# relay_interface_v4.net
KiCad netlist of a schematic drawn in EAGLE
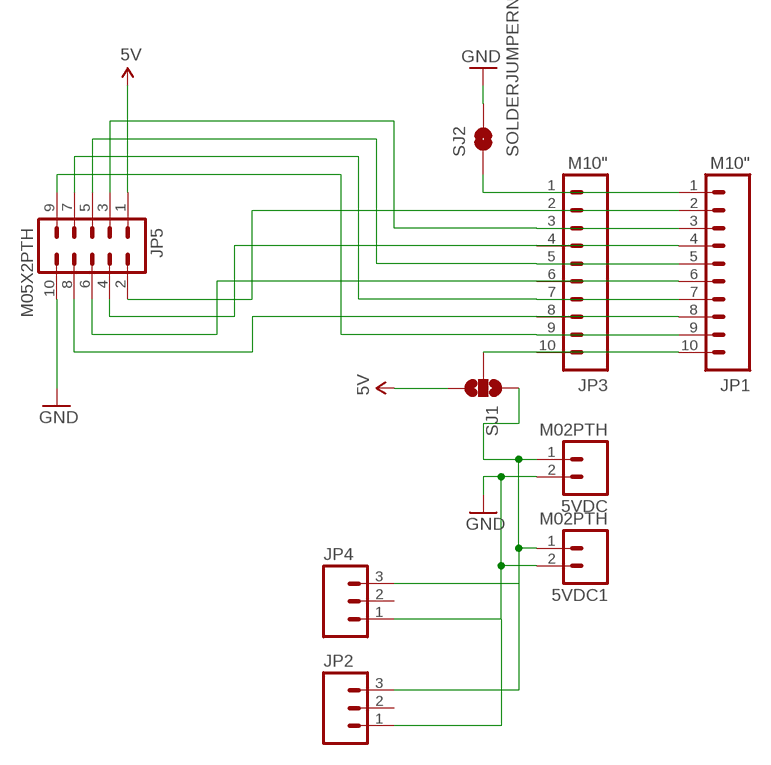
[diagram p0: schematic, sheet 1]

(export (version "E")
  (design (tool "Eeschema 10.0.6"))
  (components
    (comp (ref "5VDC")
      (value "M02PTH")
      (footprint "eagle-import:1X02")
      (libsource (lib "eagle-import") (part "M02PTH"))
    )
    (comp (ref "5VDC1")
      (value "M02PTH")
      (footprint "eagle-import:1X02")
      (libsource (lib "eagle-import") (part "M02PTH"))
    )
    (comp (ref "JP1")
      (value "M10\"")
      (footprint "eagle-import:1X10")
      (libsource (lib "eagle-import") (part "M10{dblquote}"))
    )
    (comp (ref "JP2")
      (value "M03PTH")
      (footprint "eagle-import:1X03")
      (libsource (lib "eagle-import") (part "M03PTH"))
    )
    (comp (ref "JP3")
      (value "M10\"")
      (footprint "eagle-import:1X10")
      (libsource (lib "eagle-import") (part "M10{dblquote}"))
    )
    (comp (ref "JP4")
      (value "M03PTH")
      (footprint "eagle-import:1X03")
      (libsource (lib "eagle-import") (part "M03PTH"))
    )
    (comp (ref "JP5")
      (value "M05X2PTH")
      (footprint "eagle-import:AVR_ICSP")
      (libsource (lib "eagle-import") (part "M05X2PTH"))
    )
    (comp (ref "SJ1")
      (value "SOLDERJUMPER_2WAYS")
      (footprint "eagle-import:SJ_3")
      (libsource (lib "eagle-import") (part "SOLDERJUMPER_2WAYS"))
    )
    (comp (ref "SJ2")
      (value "SOLDERJUMPERNO")
      (footprint "eagle-import:SJ_2S-NO")
      (libsource (lib "eagle-import") (part "SOLDERJUMPERNO"))
    )
  )
  (nets
    (net (code "1") (name "5V") (class "Default")
      (node (ref "JP5") (pin "1") (pinfunction "1_1") (pintype "passive"))
      (node (ref "SJ1") (pin "3") (pinfunction "3_3") (pintype "passive"))
    )
    (net (code "2") (name "GND") (class "Default")
      (node (ref "5VDC") (pin "2") (pinfunction "2_2") (pintype "passive"))
      (node (ref "5VDC1") (pin "2") (pinfunction "2_2") (pintype "passive"))
      (node (ref "JP2") (pin "1") (pinfunction "1_1") (pintype "passive"))
      (node (ref "JP4") (pin "1") (pinfunction "1_1") (pintype "passive"))
      (node (ref "JP5") (pin "10") (pinfunction "10_10") (pintype "passive"))
      (node (ref "SJ2") (pin "2") (pinfunction "2_2") (pintype "passive"))
    )
    (net (code "3") (name "Net-(5VDC-Pad1)") (class "Default")
      (node (ref "5VDC") (pin "1") (pinfunction "1_1") (pintype "passive"))
      (node (ref "5VDC1") (pin "1") (pinfunction "1_1") (pintype "passive"))
      (node (ref "JP2") (pin "3") (pinfunction "3_3") (pintype "passive"))
      (node (ref "JP4") (pin "3") (pinfunction "3_3") (pintype "passive"))
      (node (ref "SJ1") (pin "1") (pinfunction "1_1") (pintype "passive"))
    )
    (net (code "4") (name "Net-(JP1-Pad1)") (class "Default")
      (node (ref "JP1") (pin "1") (pinfunction "1_1") (pintype "passive"))
      (node (ref "JP3") (pin "1") (pinfunction "1_1") (pintype "passive"))
      (node (ref "SJ2") (pin "1") (pinfunction "1_1") (pintype "passive"))
    )
    (net (code "5") (name "Net-(JP1-Pad2)") (class "Default")
      (node (ref "JP1") (pin "2") (pinfunction "2_2") (pintype "passive"))
      (node (ref "JP3") (pin "2") (pinfunction "2_2") (pintype "passive"))
      (node (ref "JP5") (pin "2") (pinfunction "2_2") (pintype "passive"))
    )
    (net (code "6") (name "Net-(JP1-Pad3)") (class "Default")
      (node (ref "JP1") (pin "3") (pinfunction "3_3") (pintype "passive"))
      (node (ref "JP3") (pin "3") (pinfunction "3_3") (pintype "passive"))
      (node (ref "JP5") (pin "3") (pinfunction "3_3") (pintype "passive"))
    )
    (net (code "7") (name "Net-(JP1-Pad4)") (class "Default")
      (node (ref "JP1") (pin "4") (pinfunction "4_4") (pintype "passive"))
      (node (ref "JP3") (pin "4") (pinfunction "4_4") (pintype "passive"))
      (node (ref "JP5") (pin "4") (pinfunction "4_4") (pintype "passive"))
    )
    (net (code "8") (name "Net-(JP1-Pad5)") (class "Default")
      (node (ref "JP1") (pin "5") (pinfunction "5_5") (pintype "passive"))
      (node (ref "JP3") (pin "5") (pinfunction "5_5") (pintype "passive"))
      (node (ref "JP5") (pin "5") (pinfunction "5_5") (pintype "passive"))
    )
    (net (code "9") (name "Net-(JP1-Pad6)") (class "Default")
      (node (ref "JP1") (pin "6") (pinfunction "6_6") (pintype "passive"))
      (node (ref "JP3") (pin "6") (pinfunction "6_6") (pintype "passive"))
      (node (ref "JP5") (pin "6") (pinfunction "6_6") (pintype "passive"))
    )
    (net (code "10") (name "Net-(JP1-Pad7)") (class "Default")
      (node (ref "JP1") (pin "7") (pinfunction "7_7") (pintype "passive"))
      (node (ref "JP3") (pin "7") (pinfunction "7_7") (pintype "passive"))
      (node (ref "JP5") (pin "7") (pinfunction "7_7") (pintype "passive"))
    )
    (net (code "11") (name "Net-(JP1-Pad8)") (class "Default")
      (node (ref "JP1") (pin "8") (pinfunction "8_8") (pintype "passive"))
      (node (ref "JP3") (pin "8") (pinfunction "8_8") (pintype "passive"))
      (node (ref "JP5") (pin "8") (pinfunction "8_8") (pintype "passive"))
    )
    (net (code "12") (name "Net-(JP1-Pad9)") (class "Default")
      (node (ref "JP1") (pin "9") (pinfunction "9_9") (pintype "passive"))
      (node (ref "JP3") (pin "9") (pinfunction "9_9") (pintype "passive"))
      (node (ref "JP5") (pin "9") (pinfunction "9_9") (pintype "passive"))
    )
    (net (code "13") (name "Net-(JP1-Pad10)") (class "Default")
      (node (ref "JP1") (pin "10") (pinfunction "10_10") (pintype "passive"))
      (node (ref "JP3") (pin "10") (pinfunction "10_10") (pintype "passive"))
      (node (ref "SJ1") (pin "2") (pinfunction "2_2") (pintype "passive"))
    )
    (net (code "14") (name "unconnected-(JP2-Pad2)") (class "Default")
      (node (ref "JP2") (pin "2") (pinfunction "2_2") (pintype "passive"))
    )
    (net (code "15") (name "unconnected-(JP4-Pad2)") (class "Default")
      (node (ref "JP4") (pin "2") (pinfunction "2_2") (pintype "passive"))
    )
  )
)
